# clock.net
KiCad netlist of a schematic drawn in EAGLE
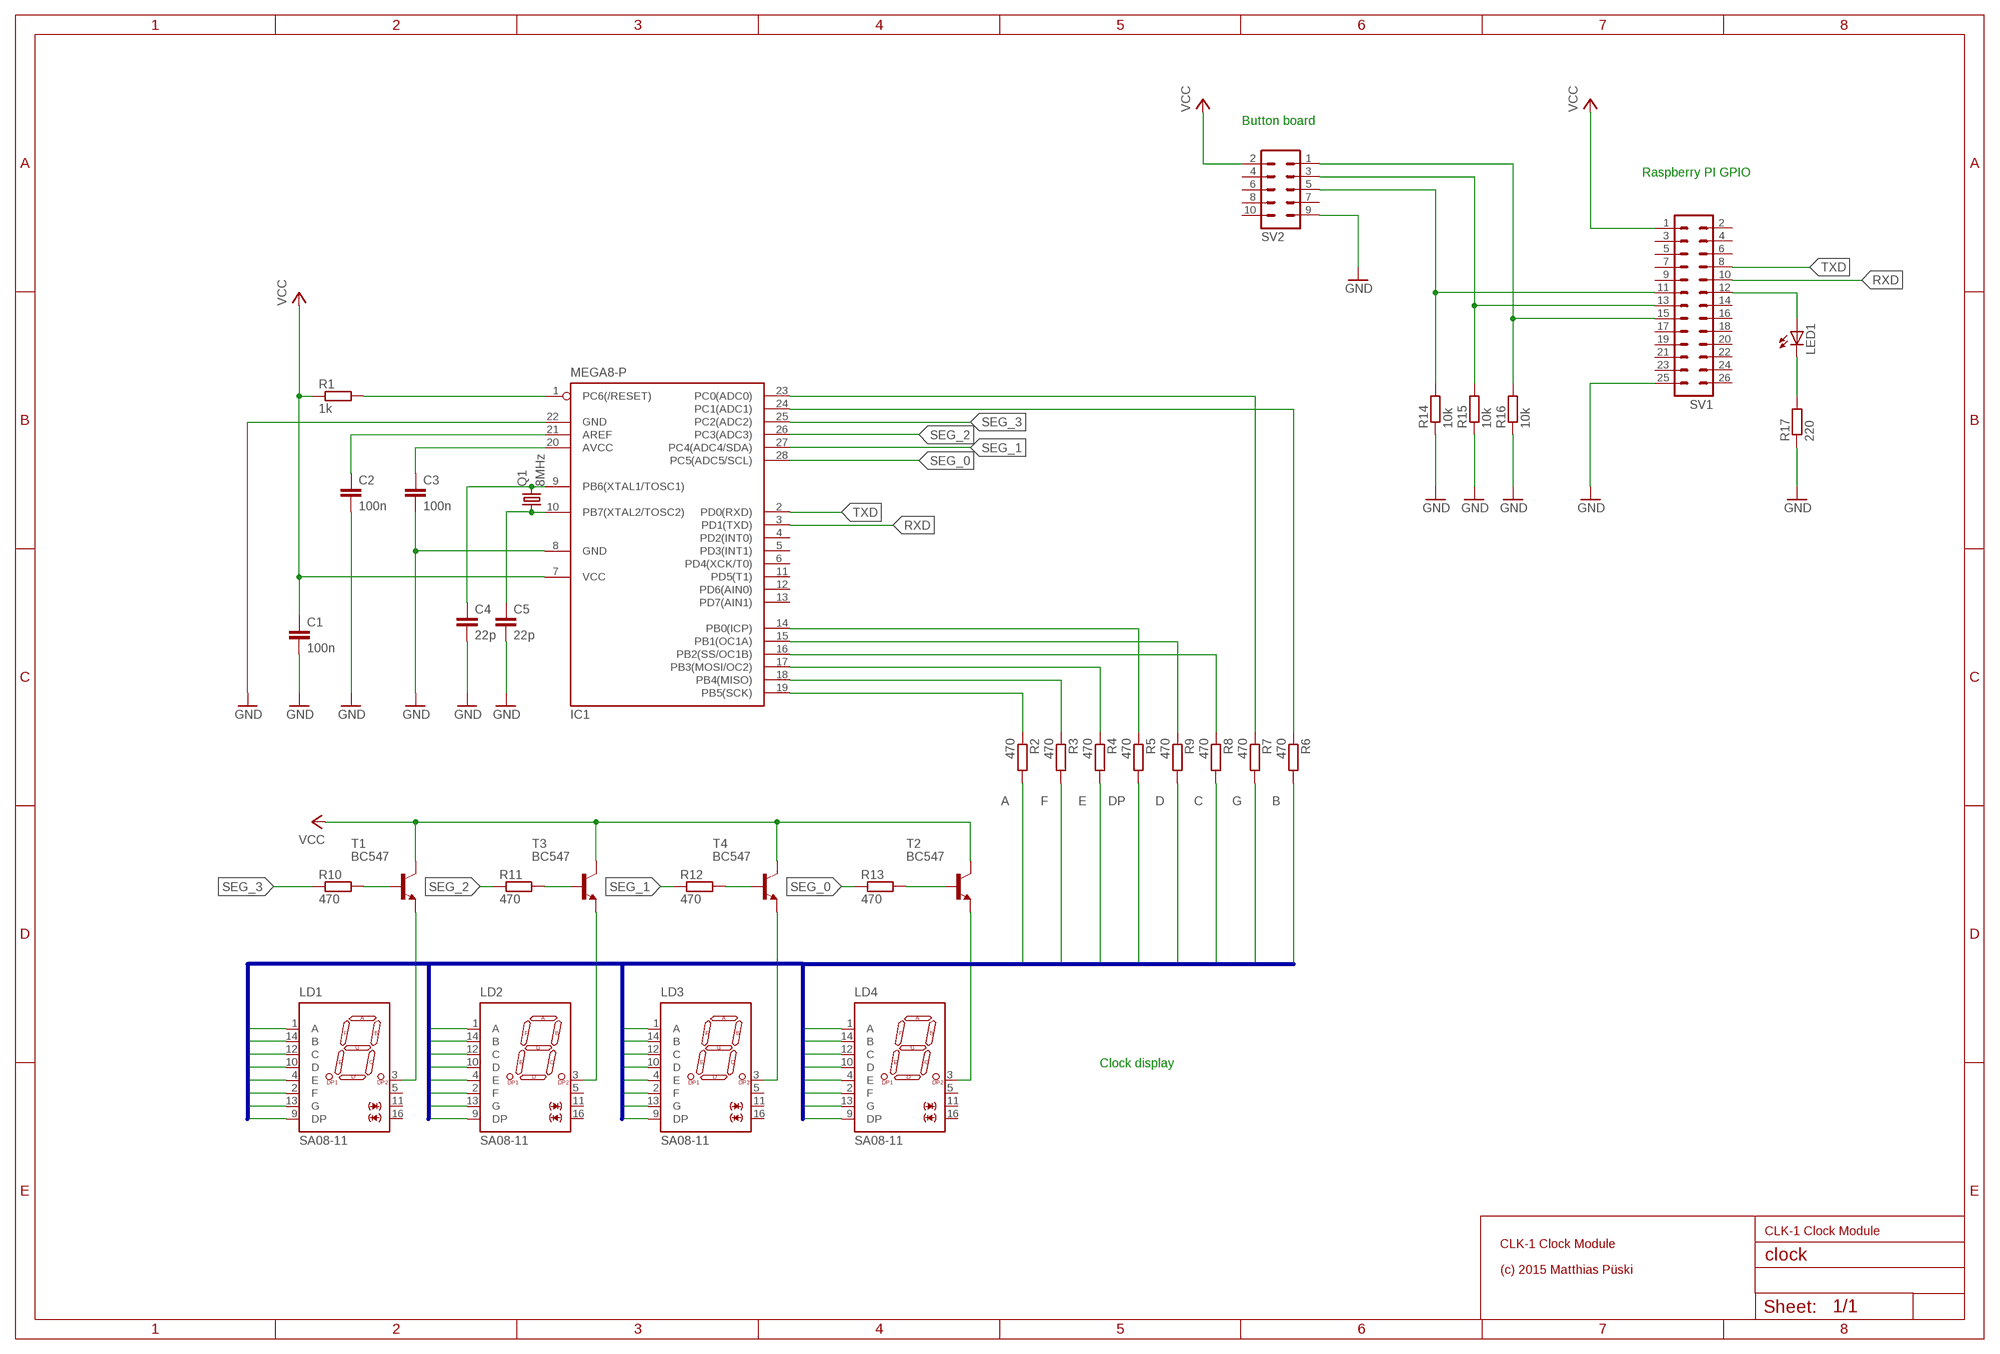
[diagram p0: schematic, sheet 1]

(export (version "E")
  (design (tool "Eeschema 10.0.6"))
  (components
    (comp (ref "C1")
      (value "100n")
      (footprint "eagle-import:C025-024X044")
      (libsource (lib "eagle-import") (part "C-EU025-024X044"))
    )
    (comp (ref "C2")
      (value "100n")
      (footprint "eagle-import:C025-024X044")
      (libsource (lib "eagle-import") (part "C-EU025-024X044"))
    )
    (comp (ref "C3")
      (value "100n")
      (footprint "eagle-import:C025-024X044")
      (libsource (lib "eagle-import") (part "C-EU025-024X044"))
    )
    (comp (ref "C4")
      (value "22p")
      (footprint "eagle-import:C025-024X044")
      (libsource (lib "eagle-import") (part "C-EU025-024X044"))
    )
    (comp (ref "C5")
      (value "22p")
      (footprint "eagle-import:C025-024X044")
      (libsource (lib "eagle-import") (part "C-EU025-024X044"))
    )
    (comp (ref "IC1")
      (value "MEGA8-P")
      (footprint "eagle-import:DIL28-3")
      (libsource (lib "eagle-import") (part "MEGA8-P"))
    )
    (comp (ref "LD1")
      (value "SA08-11")
      (footprint "eagle-import:SA08")
      (libsource (lib "eagle-import") (part "S08-11A"))
    )
    (comp (ref "LD2")
      (value "SA08-11")
      (footprint "eagle-import:SA08")
      (libsource (lib "eagle-import") (part "S08-11A"))
    )
    (comp (ref "LD3")
      (value "SA08-11")
      (footprint "eagle-import:SA08")
      (libsource (lib "eagle-import") (part "S08-11A"))
    )
    (comp (ref "LD4")
      (value "SA08-11")
      (footprint "eagle-import:SA08")
      (libsource (lib "eagle-import") (part "S08-11A"))
    )
    (comp (ref "LED1")
      (value "LED5MM")
      (footprint "eagle-import:LED5MM")
      (libsource (lib "eagle-import") (part "LED5MM"))
    )
    (comp (ref "Q1")
      (value "8MHz")
      (footprint "eagle-import:HC49_S")
      (libsource (lib "eagle-import") (part "CRYSTALHC49S"))
    )
    (comp (ref "R1")
      (value "1k")
      (footprint "eagle-import:0207_10")
      (libsource (lib "eagle-import") (part "R-EU_0207/10"))
    )
    (comp (ref "R2")
      (value "470")
      (footprint "eagle-import:0207_10")
      (libsource (lib "eagle-import") (part "R-EU_0207/10"))
    )
    (comp (ref "R3")
      (value "470")
      (footprint "eagle-import:0207_10")
      (libsource (lib "eagle-import") (part "R-EU_0207/10"))
    )
    (comp (ref "R4")
      (value "470")
      (footprint "eagle-import:0207_10")
      (libsource (lib "eagle-import") (part "R-EU_0207/10"))
    )
    (comp (ref "R5")
      (value "470")
      (footprint "eagle-import:0207_10")
      (libsource (lib "eagle-import") (part "R-EU_0207/10"))
    )
    (comp (ref "R6")
      (value "470")
      (footprint "eagle-import:0207_10")
      (libsource (lib "eagle-import") (part "R-EU_0207/10"))
    )
    (comp (ref "R7")
      (value "470")
      (footprint "eagle-import:0207_10")
      (libsource (lib "eagle-import") (part "R-EU_0207/10"))
    )
    (comp (ref "R8")
      (value "470")
      (footprint "eagle-import:0207_10")
      (libsource (lib "eagle-import") (part "R-EU_0207/10"))
    )
    (comp (ref "R9")
      (value "470")
      (footprint "eagle-import:0207_10")
      (libsource (lib "eagle-import") (part "R-EU_0207/10"))
    )
    (comp (ref "R10")
      (value "470")
      (footprint "eagle-import:0207_10")
      (libsource (lib "eagle-import") (part "R-EU_0207/10"))
    )
    (comp (ref "R11")
      (value "470")
      (footprint "eagle-import:0207_10")
      (libsource (lib "eagle-import") (part "R-EU_0207/10"))
    )
    (comp (ref "R12")
      (value "470")
      (footprint "eagle-import:0207_10")
      (libsource (lib "eagle-import") (part "R-EU_0207/10"))
    )
    (comp (ref "R13")
      (value "470")
      (footprint "eagle-import:0207_10")
      (libsource (lib "eagle-import") (part "R-EU_0207/10"))
    )
    (comp (ref "R14")
      (value "10k")
      (footprint "eagle-import:0207_10")
      (libsource (lib "eagle-import") (part "R-EU_0207/10"))
    )
    (comp (ref "R15")
      (value "10k")
      (footprint "eagle-import:0207_10")
      (libsource (lib "eagle-import") (part "R-EU_0207/10"))
    )
    (comp (ref "R16")
      (value "10k")
      (footprint "eagle-import:0207_10")
      (libsource (lib "eagle-import") (part "R-EU_0207/10"))
    )
    (comp (ref "R17")
      (value "220")
      (footprint "eagle-import:0207_10")
      (libsource (lib "eagle-import") (part "R-EU_0207/10"))
    )
    (comp (ref "SV1")
      (value "ML26L")
      (footprint "eagle-import:ML26L")
      (libsource (lib "eagle-import") (part "ML26L"))
    )
    (comp (ref "SV2")
      (value "ML10L")
      (footprint "eagle-import:ML10L")
      (libsource (lib "eagle-import") (part "ML10L"))
    )
    (comp (ref "T1")
      (value "BC547")
      (footprint "eagle-import:TO92")
      (libsource (lib "eagle-import") (part "BC547"))
    )
    (comp (ref "T2")
      (value "BC547")
      (footprint "eagle-import:TO92")
      (libsource (lib "eagle-import") (part "BC547"))
    )
    (comp (ref "T3")
      (value "BC547")
      (footprint "eagle-import:TO92")
      (libsource (lib "eagle-import") (part "BC547"))
    )
    (comp (ref "T4")
      (value "BC547")
      (footprint "eagle-import:TO92")
      (libsource (lib "eagle-import") (part "BC547"))
    )
  )
  (nets
    (net (code "1") (name "/A") (class "Default")
      (node (ref "LD1") (pin "1") (pinfunction "A_1") (pintype "passive"))
      (node (ref "LD2") (pin "1") (pinfunction "A_1") (pintype "passive"))
      (node (ref "LD3") (pin "1") (pinfunction "A_1") (pintype "passive"))
      (node (ref "LD4") (pin "1") (pinfunction "A_1") (pintype "passive"))
      (node (ref "R2") (pin "2") (pinfunction "2_2") (pintype "passive"))
    )
    (net (code "2") (name "/B") (class "Default")
      (node (ref "LD1") (pin "14") (pinfunction "B_14") (pintype "passive"))
      (node (ref "LD2") (pin "14") (pinfunction "B_14") (pintype "passive"))
      (node (ref "LD3") (pin "14") (pinfunction "B_14") (pintype "passive"))
      (node (ref "LD4") (pin "14") (pinfunction "B_14") (pintype "passive"))
      (node (ref "R6") (pin "2") (pinfunction "2_2") (pintype "passive"))
    )
    (net (code "3") (name "/C") (class "Default")
      (node (ref "LD1") (pin "12") (pinfunction "C_12") (pintype "passive"))
      (node (ref "LD2") (pin "12") (pinfunction "C_12") (pintype "passive"))
      (node (ref "LD3") (pin "12") (pinfunction "C_12") (pintype "passive"))
      (node (ref "LD4") (pin "12") (pinfunction "C_12") (pintype "passive"))
      (node (ref "R8") (pin "2") (pinfunction "2_2") (pintype "passive"))
    )
    (net (code "4") (name "/D") (class "Default")
      (node (ref "LD1") (pin "10") (pinfunction "D_10") (pintype "passive"))
      (node (ref "LD2") (pin "10") (pinfunction "D_10") (pintype "passive"))
      (node (ref "LD3") (pin "10") (pinfunction "D_10") (pintype "passive"))
      (node (ref "LD4") (pin "10") (pinfunction "D_10") (pintype "passive"))
      (node (ref "R9") (pin "2") (pinfunction "2_2") (pintype "passive"))
    )
    (net (code "5") (name "/DP") (class "Default")
      (node (ref "LD1") (pin "9") (pinfunction "DP_9") (pintype "passive"))
      (node (ref "LD2") (pin "9") (pinfunction "DP_9") (pintype "passive"))
      (node (ref "LD3") (pin "9") (pinfunction "DP_9") (pintype "passive"))
      (node (ref "LD4") (pin "9") (pinfunction "DP_9") (pintype "passive"))
      (node (ref "R5") (pin "2") (pinfunction "2_2") (pintype "passive"))
    )
    (net (code "6") (name "/E") (class "Default")
      (node (ref "LD1") (pin "4") (pinfunction "E_4") (pintype "passive"))
      (node (ref "LD2") (pin "4") (pinfunction "E_4") (pintype "passive"))
      (node (ref "LD3") (pin "4") (pinfunction "E_4") (pintype "passive"))
      (node (ref "LD4") (pin "4") (pinfunction "E_4") (pintype "passive"))
      (node (ref "R4") (pin "2") (pinfunction "2_2") (pintype "passive"))
    )
    (net (code "7") (name "/F") (class "Default")
      (node (ref "LD1") (pin "2") (pinfunction "F_2") (pintype "passive"))
      (node (ref "LD2") (pin "2") (pinfunction "F_2") (pintype "passive"))
      (node (ref "LD3") (pin "2") (pinfunction "F_2") (pintype "passive"))
      (node (ref "LD4") (pin "2") (pinfunction "F_2") (pintype "passive"))
      (node (ref "R3") (pin "2") (pinfunction "2_2") (pintype "passive"))
    )
    (net (code "8") (name "/G") (class "Default")
      (node (ref "LD1") (pin "13") (pinfunction "G_13") (pintype "passive"))
      (node (ref "LD2") (pin "13") (pinfunction "G_13") (pintype "passive"))
      (node (ref "LD3") (pin "13") (pinfunction "G_13") (pintype "passive"))
      (node (ref "LD4") (pin "13") (pinfunction "G_13") (pintype "passive"))
      (node (ref "R7") (pin "2") (pinfunction "2_2") (pintype "passive"))
    )
    (net (code "9") (name "GND") (class "Default")
      (node (ref "C1") (pin "2") (pinfunction "2_2") (pintype "passive"))
      (node (ref "C2") (pin "2") (pinfunction "2_2") (pintype "passive"))
      (node (ref "C3") (pin "2") (pinfunction "2_2") (pintype "passive"))
      (node (ref "C4") (pin "2") (pinfunction "2_2") (pintype "passive"))
      (node (ref "C5") (pin "2") (pinfunction "2_2") (pintype "passive"))
      (node (ref "IC1") (pin "22") (pinfunction "GND_22") (pintype "power_in"))
      (node (ref "IC1") (pin "8") (pinfunction "GND_8") (pintype "power_in"))
      (node (ref "R14") (pin "1") (pinfunction "1_1") (pintype "passive"))
      (node (ref "R15") (pin "1") (pinfunction "1_1") (pintype "passive"))
      (node (ref "R16") (pin "1") (pinfunction "1_1") (pintype "passive"))
      (node (ref "R17") (pin "1") (pinfunction "1_1") (pintype "passive"))
      (node (ref "SV1") (pin "25") (pinfunction "25_25") (pintype "passive"))
      (node (ref "SV2") (pin "9") (pinfunction "9_9") (pintype "passive"))
    )
    (net (code "10") (name "Net-(IC1-AREF)") (class "Default")
      (node (ref "C2") (pin "1") (pinfunction "1_1") (pintype "passive"))
      (node (ref "IC1") (pin "21") (pinfunction "AREF_21") (pintype "passive"))
    )
    (net (code "11") (name "Net-(IC1-AVCC)") (class "Default")
      (node (ref "C3") (pin "1") (pinfunction "1_1") (pintype "passive"))
      (node (ref "IC1") (pin "20") (pinfunction "AVCC_20") (pintype "power_in"))
    )
    (net (code "12") (name "Net-(IC1-PB0(ICP))") (class "Default")
      (node (ref "IC1") (pin "14") (pinfunction "PB0(ICP)_14") (pintype "bidirectional"))
      (node (ref "R5") (pin "1") (pinfunction "1_1") (pintype "passive"))
    )
    (net (code "13") (name "Net-(IC1-PB1(OC1A))") (class "Default")
      (node (ref "IC1") (pin "15") (pinfunction "PB1(OC1A)_15") (pintype "bidirectional"))
      (node (ref "R9") (pin "1") (pinfunction "1_1") (pintype "passive"))
    )
    (net (code "14") (name "Net-(IC1-PB2(SS{slash}OC1B))") (class "Default")
      (node (ref "IC1") (pin "16") (pinfunction "PB2(SS/OC1B)_16") (pintype "bidirectional"))
      (node (ref "R8") (pin "1") (pinfunction "1_1") (pintype "passive"))
    )
    (net (code "15") (name "Net-(IC1-PB3(MOSI{slash}OC2))") (class "Default")
      (node (ref "IC1") (pin "17") (pinfunction "PB3(MOSI/OC2)_17") (pintype "bidirectional"))
      (node (ref "R4") (pin "1") (pinfunction "1_1") (pintype "passive"))
    )
    (net (code "16") (name "Net-(IC1-PB4(MISO))") (class "Default")
      (node (ref "IC1") (pin "18") (pinfunction "PB4(MISO)_18") (pintype "bidirectional"))
      (node (ref "R3") (pin "1") (pinfunction "1_1") (pintype "passive"))
    )
    (net (code "17") (name "Net-(IC1-PB5(SCK))") (class "Default")
      (node (ref "IC1") (pin "19") (pinfunction "PB5(SCK)_19") (pintype "bidirectional"))
      (node (ref "R2") (pin "1") (pinfunction "1_1") (pintype "passive"))
    )
    (net (code "18") (name "Net-(IC1-PB6(XTAL1{slash}TOSC1))") (class "Default")
      (node (ref "C4") (pin "1") (pinfunction "1_1") (pintype "passive"))
      (node (ref "IC1") (pin "9") (pinfunction "PB6(XTAL1/TOSC1)_9") (pintype "bidirectional"))
      (node (ref "Q1") (pin "2") (pinfunction "2_2") (pintype "passive"))
    )
    (net (code "19") (name "Net-(IC1-PB7(XTAL2{slash}TOSC2))") (class "Default")
      (node (ref "C5") (pin "1") (pinfunction "1_1") (pintype "passive"))
      (node (ref "IC1") (pin "10") (pinfunction "PB7(XTAL2/TOSC2)_10") (pintype "bidirectional"))
      (node (ref "Q1") (pin "1") (pinfunction "1_1") (pintype "passive"))
    )
    (net (code "20") (name "Net-(IC1-PC0(ADC0))") (class "Default")
      (node (ref "IC1") (pin "23") (pinfunction "PC0(ADC0)_23") (pintype "bidirectional"))
      (node (ref "R7") (pin "1") (pinfunction "1_1") (pintype "passive"))
    )
    (net (code "21") (name "Net-(IC1-PC1(ADC1))") (class "Default")
      (node (ref "IC1") (pin "24") (pinfunction "PC1(ADC1)_24") (pintype "bidirectional"))
      (node (ref "R6") (pin "1") (pinfunction "1_1") (pintype "passive"))
    )
    (net (code "22") (name "Net-(IC1-PC6({slash}RESET))") (class "Default")
      (node (ref "IC1") (pin "1") (pinfunction "PC6(/RESET)_1") (pintype "bidirectional"))
      (node (ref "R1") (pin "2") (pinfunction "2_2") (pintype "passive"))
    )
    (net (code "23") (name "Net-(LED1-C)") (class "Default")
      (node (ref "LED1") (pin "K") (pinfunction "C_K") (pintype "passive"))
      (node (ref "R17") (pin "2") (pinfunction "2_2") (pintype "passive"))
    )
    (net (code "24") (name "Net-(LED1-PadA)") (class "Default")
      (node (ref "LED1") (pin "A") (pinfunction "A_A") (pintype "passive"))
      (node (ref "SV1") (pin "12") (pinfunction "12_12") (pintype "passive"))
    )
    (net (code "25") (name "Net-(R14-Pad2)") (class "Default")
      (node (ref "R14") (pin "2") (pinfunction "2_2") (pintype "passive"))
      (node (ref "SV1") (pin "11") (pinfunction "11_11") (pintype "passive"))
      (node (ref "SV2") (pin "5") (pinfunction "5_5") (pintype "passive"))
    )
    (net (code "26") (name "Net-(R15-Pad2)") (class "Default")
      (node (ref "R15") (pin "2") (pinfunction "2_2") (pintype "passive"))
      (node (ref "SV1") (pin "13") (pinfunction "13_13") (pintype "passive"))
      (node (ref "SV2") (pin "3") (pinfunction "3_3") (pintype "passive"))
    )
    (net (code "27") (name "Net-(R16-Pad2)") (class "Default")
      (node (ref "R16") (pin "2") (pinfunction "2_2") (pintype "passive"))
      (node (ref "SV1") (pin "15") (pinfunction "15_15") (pintype "passive"))
      (node (ref "SV2") (pin "1") (pinfunction "1_1") (pintype "passive"))
    )
    (net (code "28") (name "Net-(T1-B)") (class "Default")
      (node (ref "R10") (pin "2") (pinfunction "2_2") (pintype "passive"))
      (node (ref "T1") (pin "2") (pinfunction "B_2") (pintype "passive"))
    )
    (net (code "29") (name "Net-(T1-E)") (class "Default")
      (node (ref "LD1") (pin "3") (pinfunction "AK_3") (pintype "passive"))
      (node (ref "T1") (pin "1") (pinfunction "E_1") (pintype "passive"))
    )
    (net (code "30") (name "Net-(T2-B)") (class "Default")
      (node (ref "R13") (pin "2") (pinfunction "2_2") (pintype "passive"))
      (node (ref "T2") (pin "2") (pinfunction "B_2") (pintype "passive"))
    )
    (net (code "31") (name "Net-(T2-E)") (class "Default")
      (node (ref "LD4") (pin "3") (pinfunction "AK_3") (pintype "passive"))
      (node (ref "T2") (pin "1") (pinfunction "E_1") (pintype "passive"))
    )
    (net (code "32") (name "Net-(T3-B)") (class "Default")
      (node (ref "R11") (pin "2") (pinfunction "2_2") (pintype "passive"))
      (node (ref "T3") (pin "2") (pinfunction "B_2") (pintype "passive"))
    )
    (net (code "33") (name "Net-(T3-E)") (class "Default")
      (node (ref "LD2") (pin "3") (pinfunction "AK_3") (pintype "passive"))
      (node (ref "T3") (pin "1") (pinfunction "E_1") (pintype "passive"))
    )
    (net (code "34") (name "Net-(T4-B)") (class "Default")
      (node (ref "R12") (pin "2") (pinfunction "2_2") (pintype "passive"))
      (node (ref "T4") (pin "2") (pinfunction "B_2") (pintype "passive"))
    )
    (net (code "35") (name "Net-(T4-E)") (class "Default")
      (node (ref "LD3") (pin "3") (pinfunction "AK_3") (pintype "passive"))
      (node (ref "T4") (pin "1") (pinfunction "E_1") (pintype "passive"))
    )
    (net (code "36") (name "RXD") (class "Default")
      (node (ref "IC1") (pin "3") (pinfunction "PD1(TXD)_3") (pintype "bidirectional"))
      (node (ref "SV1") (pin "10") (pinfunction "10_10") (pintype "passive"))
    )
    (net (code "37") (name "SEG_0") (class "Default")
      (node (ref "IC1") (pin "28") (pinfunction "PC5(ADC5/SCL)_28") (pintype "bidirectional"))
      (node (ref "R13") (pin "1") (pinfunction "1_1") (pintype "passive"))
    )
    (net (code "38") (name "SEG_1") (class "Default")
      (node (ref "IC1") (pin "27") (pinfunction "PC4(ADC4/SDA)_27") (pintype "bidirectional"))
      (node (ref "R12") (pin "1") (pinfunction "1_1") (pintype "passive"))
    )
    (net (code "39") (name "SEG_2") (class "Default")
      (node (ref "IC1") (pin "26") (pinfunction "PC3(ADC3)_26") (pintype "bidirectional"))
      (node (ref "R11") (pin "1") (pinfunction "1_1") (pintype "passive"))
    )
    (net (code "40") (name "SEG_3") (class "Default")
      (node (ref "IC1") (pin "25") (pinfunction "PC2(ADC2)_25") (pintype "bidirectional"))
      (node (ref "R10") (pin "1") (pinfunction "1_1") (pintype "passive"))
    )
    (net (code "41") (name "TXD") (class "Default")
      (node (ref "IC1") (pin "2") (pinfunction "PD0(RXD)_2") (pintype "bidirectional"))
      (node (ref "SV1") (pin "8") (pinfunction "8_8") (pintype "passive"))
    )
    (net (code "42") (name "VCC") (class "Default")
      (node (ref "C1") (pin "1") (pinfunction "1_1") (pintype "passive"))
      (node (ref "IC1") (pin "7") (pinfunction "VCC_7") (pintype "power_in"))
      (node (ref "R1") (pin "1") (pinfunction "1_1") (pintype "passive"))
      (node (ref "SV1") (pin "1") (pinfunction "1_1") (pintype "passive"))
      (node (ref "SV2") (pin "2") (pinfunction "2_2") (pintype "passive"))
      (node (ref "T1") (pin "3") (pinfunction "C_3") (pintype "passive"))
      (node (ref "T2") (pin "3") (pinfunction "C_3") (pintype "passive"))
      (node (ref "T3") (pin "3") (pinfunction "C_3") (pintype "passive"))
      (node (ref "T4") (pin "3") (pinfunction "C_3") (pintype "passive"))
    )
    (net (code "43") (name "unconnected-(IC1-PD2(INT0)-Pad4)") (class "Default")
      (node (ref "IC1") (pin "4") (pinfunction "PD2(INT0)_4") (pintype "bidirectional"))
    )
    (net (code "44") (name "unconnected-(IC1-PD3(INT1)-Pad5)") (class "Default")
      (node (ref "IC1") (pin "5") (pinfunction "PD3(INT1)_5") (pintype "bidirectional"))
    )
    (net (code "45") (name "unconnected-(IC1-PD4(XCK{slash}T0)-Pad6)") (class "Default")
      (node (ref "IC1") (pin "6") (pinfunction "PD4(XCK/T0)_6") (pintype "bidirectional"))
    )
    (net (code "46") (name "unconnected-(IC1-PD5(T1)-Pad11)") (class "Default")
      (node (ref "IC1") (pin "11") (pinfunction "PD5(T1)_11") (pintype "bidirectional"))
    )
    (net (code "47") (name "unconnected-(IC1-PD6(AIN0)-Pad12)") (class "Default")
      (node (ref "IC1") (pin "12") (pinfunction "PD6(AIN0)_12") (pintype "bidirectional"))
    )
    (net (code "48") (name "unconnected-(IC1-PD7(AIN1)-Pad13)") (class "Default")
      (node (ref "IC1") (pin "13") (pinfunction "PD7(AIN1)_13") (pintype "bidirectional"))
    )
    (net (code "49") (name "unconnected-(LD1-AK-Pad5)") (class "Default")
      (node (ref "LD1") (pin "5") (pinfunction "AK_5") (pintype "passive"))
    )
    (net (code "50") (name "unconnected-(LD1-AK-Pad11)") (class "Default")
      (node (ref "LD1") (pin "11") (pinfunction "AK_11") (pintype "passive"))
    )
    (net (code "51") (name "unconnected-(LD1-AK-Pad16)") (class "Default")
      (node (ref "LD1") (pin "16") (pinfunction "AK_16") (pintype "passive"))
    )
    (net (code "52") (name "unconnected-(LD2-AK-Pad5)") (class "Default")
      (node (ref "LD2") (pin "5") (pinfunction "AK_5") (pintype "passive"))
    )
    (net (code "53") (name "unconnected-(LD2-AK-Pad11)") (class "Default")
      (node (ref "LD2") (pin "11") (pinfunction "AK_11") (pintype "passive"))
    )
    (net (code "54") (name "unconnected-(LD2-AK-Pad16)") (class "Default")
      (node (ref "LD2") (pin "16") (pinfunction "AK_16") (pintype "passive"))
    )
    (net (code "55") (name "unconnected-(LD3-AK-Pad5)") (class "Default")
      (node (ref "LD3") (pin "5") (pinfunction "AK_5") (pintype "passive"))
    )
    (net (code "56") (name "unconnected-(LD3-AK-Pad11)") (class "Default")
      (node (ref "LD3") (pin "11") (pinfunction "AK_11") (pintype "passive"))
    )
    (net (code "57") (name "unconnected-(LD3-AK-Pad16)") (class "Default")
      (node (ref "LD3") (pin "16") (pinfunction "AK_16") (pintype "passive"))
    )
    (net (code "58") (name "unconnected-(LD4-AK-Pad5)") (class "Default")
      (node (ref "LD4") (pin "5") (pinfunction "AK_5") (pintype "passive"))
    )
    (net (code "59") (name "unconnected-(LD4-AK-Pad11)") (class "Default")
      (node (ref "LD4") (pin "11") (pinfunction "AK_11") (pintype "passive"))
    )
    (net (code "60") (name "unconnected-(LD4-AK-Pad16)") (class "Default")
      (node (ref "LD4") (pin "16") (pinfunction "AK_16") (pintype "passive"))
    )
    (net (code "61") (name "unconnected-(SV1-Pad2)") (class "Default")
      (node (ref "SV1") (pin "2") (pinfunction "2_2") (pintype "passive"))
    )
    (net (code "62") (name "unconnected-(SV1-Pad3)") (class "Default")
      (node (ref "SV1") (pin "3") (pinfunction "3_3") (pintype "passive"))
    )
    (net (code "63") (name "unconnected-(SV1-Pad4)") (class "Default")
      (node (ref "SV1") (pin "4") (pinfunction "4_4") (pintype "passive"))
    )
    (net (code "64") (name "unconnected-(SV1-Pad5)") (class "Default")
      (node (ref "SV1") (pin "5") (pinfunction "5_5") (pintype "passive"))
    )
    (net (code "65") (name "unconnected-(SV1-Pad6)") (class "Default")
      (node (ref "SV1") (pin "6") (pinfunction "6_6") (pintype "passive"))
    )
    (net (code "66") (name "unconnected-(SV1-Pad7)") (class "Default")
      (node (ref "SV1") (pin "7") (pinfunction "7_7") (pintype "passive"))
    )
    (net (code "67") (name "unconnected-(SV1-Pad9)") (class "Default")
      (node (ref "SV1") (pin "9") (pinfunction "9_9") (pintype "passive"))
    )
    (net (code "68") (name "unconnected-(SV1-Pad14)") (class "Default")
      (node (ref "SV1") (pin "14") (pinfunction "14_14") (pintype "passive"))
    )
    (net (code "69") (name "unconnected-(SV1-Pad16)") (class "Default")
      (node (ref "SV1") (pin "16") (pinfunction "16_16") (pintype "passive"))
    )
    (net (code "70") (name "unconnected-(SV1-Pad17)") (class "Default")
      (node (ref "SV1") (pin "17") (pinfunction "17_17") (pintype "passive"))
    )
    (net (code "71") (name "unconnected-(SV1-Pad18)") (class "Default")
      (node (ref "SV1") (pin "18") (pinfunction "18_18") (pintype "passive"))
    )
    (net (code "72") (name "unconnected-(SV1-Pad19)") (class "Default")
      (node (ref "SV1") (pin "19") (pinfunction "19_19") (pintype "passive"))
    )
    (net (code "73") (name "unconnected-(SV1-Pad20)") (class "Default")
      (node (ref "SV1") (pin "20") (pinfunction "20_20") (pintype "passive"))
    )
    (net (code "74") (name "unconnected-(SV1-Pad21)") (class "Default")
      (node (ref "SV1") (pin "21") (pinfunction "21_21") (pintype "passive"))
    )
    (net (code "75") (name "unconnected-(SV1-Pad22)") (class "Default")
      (node (ref "SV1") (pin "22") (pinfunction "22_22") (pintype "passive"))
    )
    (net (code "76") (name "unconnected-(SV1-Pad23)") (class "Default")
      (node (ref "SV1") (pin "23") (pinfunction "23_23") (pintype "passive"))
    )
    (net (code "77") (name "unconnected-(SV1-Pad24)") (class "Default")
      (node (ref "SV1") (pin "24") (pinfunction "24_24") (pintype "passive"))
    )
    (net (code "78") (name "unconnected-(SV1-Pad26)") (class "Default")
      (node (ref "SV1") (pin "26") (pinfunction "26_26") (pintype "passive"))
    )
    (net (code "79") (name "unconnected-(SV2-Pad4)") (class "Default")
      (node (ref "SV2") (pin "4") (pinfunction "4_4") (pintype "passive"))
    )
    (net (code "80") (name "unconnected-(SV2-Pad6)") (class "Default")
      (node (ref "SV2") (pin "6") (pinfunction "6_6") (pintype "passive"))
    )
    (net (code "81") (name "unconnected-(SV2-Pad7)") (class "Default")
      (node (ref "SV2") (pin "7") (pinfunction "7_7") (pintype "passive"))
    )
    (net (code "82") (name "unconnected-(SV2-Pad8)") (class "Default")
      (node (ref "SV2") (pin "8") (pinfunction "8_8") (pintype "passive"))
    )
    (net (code "83") (name "unconnected-(SV2-Pad10)") (class "Default")
      (node (ref "SV2") (pin "10") (pinfunction "10_10") (pintype "passive"))
    )
  )
)
